# PWR_MGMT.net
KiCad netlist of a schematic drawn in Altium Designer
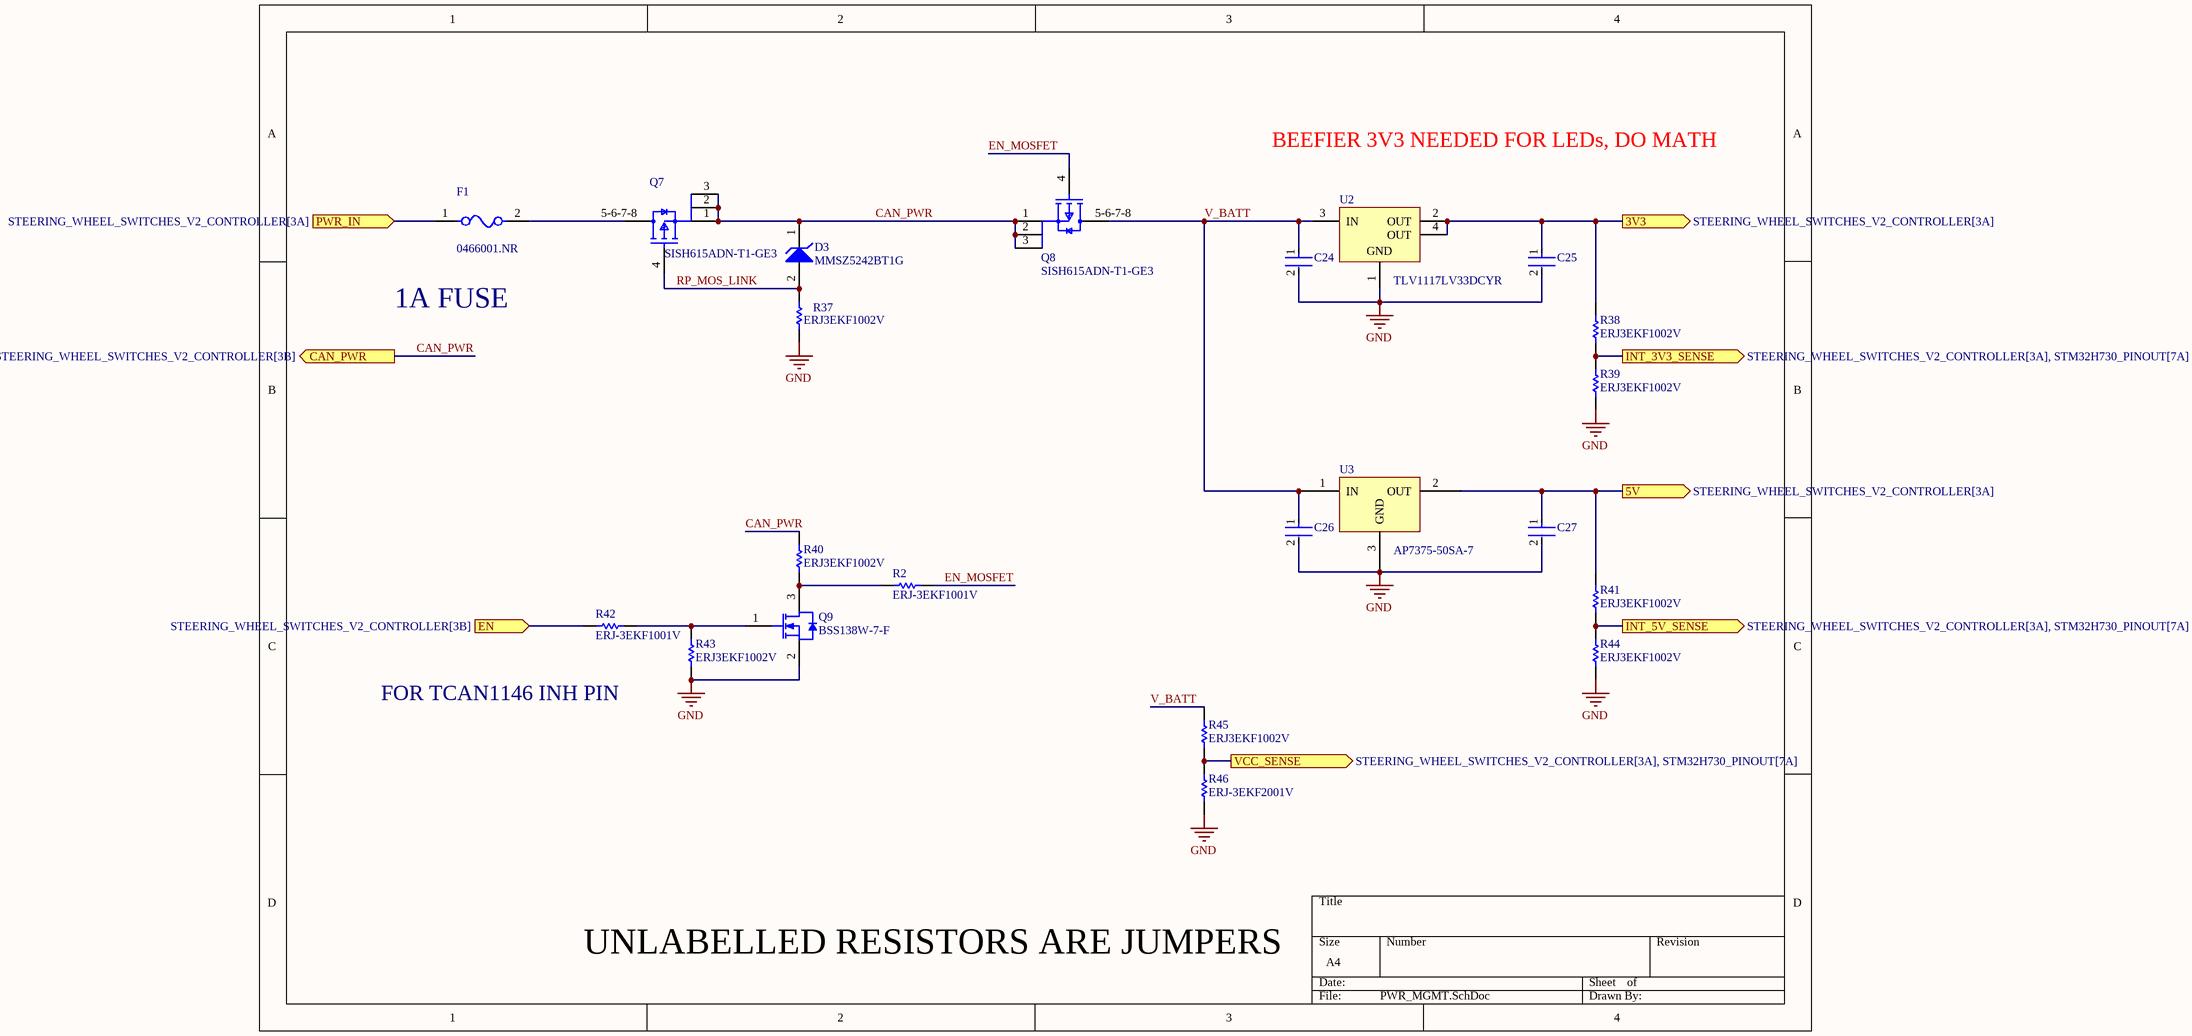
[diagram p0: PWR_MGMT.SchDoc]

(export (version "E")
  (design (tool "Eeschema 10.0.6"))
  (components
    (comp (ref "C24")
      (value "GRM188R61E106KA73D")
      (footprint "FP-GRM188-0_2-IPC_A")
      (description "Chip Multilayer Ceramic Capacitors for General Purpose, 0603, 10uF, X5R, 15%, 10%, 25V")
      (libsource (lib "Altium Content Vault") (part "11868f565c42a9108669ba33697ecf6"))
    )
    (comp (ref "C25")
      (value "GRM188R61E106KA73D")
      (footprint "FP-GRM188-0_2-IPC_A")
      (description "Chip Multilayer Ceramic Capacitors for General Purpose, 0603, 10uF, X5R, 15%, 10%, 25V")
      (libsource (lib "Altium Content Vault") (part "11868f565c42a9108669ba33697ecf6"))
    )
    (comp (ref "C26")
      (value "GRM188R61E106KA73D")
      (footprint "FP-GRM188-0_2-IPC_A")
      (description "Chip Multilayer Ceramic Capacitors for General Purpose, 0603, 10uF, X5R, 15%, 10%, 25V")
      (libsource (lib "Altium Content Vault") (part "11868f565c42a9108669ba33697ecf6"))
    )
    (comp (ref "C27")
      (value "GRM188R61E106KA73D")
      (footprint "FP-GRM188-0_2-IPC_A")
      (description "Chip Multilayer Ceramic Capacitors for General Purpose, 0603, 10uF, X5R, 15%, 10%, 25V")
      (libsource (lib "Altium Content Vault") (part "11868f565c42a9108669ba33697ecf6"))
    )
    (comp (ref "D3")
      (value "MMSZ5242BT1G")
      (footprint "ONSC-SOD-123-2-425-04_V")
      (description "Zener Voltage Regulator, 500 mW, 2-Pin SOD-123, Pb-Free, Tape and Reel")
      (fields (field (name "MANUFACTURER") "On Semiconductor"))
      (libsource (lib "Altium Content Vault") (part "ONSC-K1A2-2"))
    )
    (comp (ref "F1")
      (value "0466001.NR")
      (footprint "FP-0466-MFG")
      (description "FUSE BOARD MNT 1A 63VAC/VDC 1206")
      (fields
        (field (name "MANUFACTURER") "Littelfuse Inc")
        (field (name "OCTOPART") "https://octopart.com/0466001.nr-littelfuse-566005")
      )
      (libsource (lib "Altium Content Vault") (part "5bcf9b9f640e542cf0359d10258e979"))
    )
    (comp (ref "Q7")
      (value "SISH615ADN-T1-GE3")
      (footprint "SISH615ADN-T1-GE3-Footprint-1")
      (description "Trans MOSFET P-CH 20V 22.1A 8-Pin PowerPAK 1212 EP T/R")
      (libsource (lib "Space Concordia") (part "CMP-013-00036-4"))
    )
    (comp (ref "Q8")
      (value "SISH615ADN-T1-GE3")
      (footprint "SISH615ADN-T1-GE3-Footprint-1")
      (description "Trans MOSFET P-CH 20V 22.1A 8-Pin PowerPAK 1212 EP T/R")
      (libsource (lib "Space Concordia") (part "CMP-013-00036-4"))
    )
    (comp (ref "Q9")
      (value "BSS138W-7-F")
      (footprint "DIOD-SOT323-3_V")
      (fields (field (name "MANUFACTURER") "DiodesIncorporated"))
      (libsource (lib "Altium Content Vault") (part "NEMOS-GSD-3"))
    )
    (comp (ref "R2")
      (value "ERJ-3EKF1001V")
      (footprint "RESC1608X55X30LL15T15")
      (fields (field (name "MANUFACTURER") "Panasonic"))
      (libsource (lib "Altium Content Vault") (part "RES"))
    )
    (comp (ref "R37")
      (value "ERJ3EKF1002V")
      (footprint "RESC1609X55X30LL15T15")
      (description "Chip Resistor, 10 KOhm, +/- 1%, 0.1 W, -55 to 155 degC, 0603 (1608 Metric), RoHS, Tape and Reel")
      (fields (field (name "TOLERANCE") "1%") (field (name "MANUFACTURER") "Panasonic"))
      (libsource (lib "Altium Content Vault") (part "RES-2"))
    )
    (comp (ref "R38")
      (value "ERJ3EKF1002V")
      (footprint "RESC1609X55X30LL15T15")
      (description "Chip Resistor, 10 KOhm, +/- 1%, 0.1 W, -55 to 155 degC, 0603 (1608 Metric), RoHS, Tape and Reel")
      (fields (field (name "TOLERANCE") "1%") (field (name "MANUFACTURER") "Panasonic"))
      (libsource (lib "Altium Content Vault") (part "RES-2"))
    )
    (comp (ref "R39")
      (value "ERJ3EKF1002V")
      (footprint "RESC1609X55X30LL15T15")
      (description "Chip Resistor, 10 KOhm, +/- 1%, 0.1 W, -55 to 155 degC, 0603 (1608 Metric), RoHS, Tape and Reel")
      (fields (field (name "TOLERANCE") "1%") (field (name "MANUFACTURER") "Panasonic"))
      (libsource (lib "Altium Content Vault") (part "RES-2"))
    )
    (comp (ref "R40")
      (value "ERJ3EKF1002V")
      (footprint "RESC1609X55X30LL15T15")
      (description "Chip Resistor, 10 KOhm, +/- 1%, 0.1 W, -55 to 155 degC, 0603 (1608 Metric), RoHS, Tape and Reel")
      (fields (field (name "TOLERANCE") "1%") (field (name "MANUFACTURER") "Panasonic"))
      (libsource (lib "Altium Content Vault") (part "RES-2"))
    )
    (comp (ref "R41")
      (value "ERJ3EKF1002V")
      (footprint "RESC1609X55X30LL15T15")
      (description "Chip Resistor, 10 KOhm, +/- 1%, 0.1 W, -55 to 155 degC, 0603 (1608 Metric), RoHS, Tape and Reel")
      (fields (field (name "TOLERANCE") "1%") (field (name "MANUFACTURER") "Panasonic"))
      (libsource (lib "Altium Content Vault") (part "RES-2"))
    )
    (comp (ref "R42")
      (value "ERJ-3EKF1001V")
      (footprint "RESC1608X55X30LL15T15")
      (fields (field (name "MANUFACTURER") "Panasonic"))
      (libsource (lib "Altium Content Vault") (part "RES"))
    )
    (comp (ref "R43")
      (value "ERJ3EKF1002V")
      (footprint "RESC1609X55X30LL15T15")
      (description "Chip Resistor, 10 KOhm, +/- 1%, 0.1 W, -55 to 155 degC, 0603 (1608 Metric), RoHS, Tape and Reel")
      (fields (field (name "TOLERANCE") "1%") (field (name "MANUFACTURER") "Panasonic"))
      (libsource (lib "Altium Content Vault") (part "RES-2"))
    )
    (comp (ref "R44")
      (value "ERJ3EKF1002V")
      (footprint "RESC1609X55X30LL15T15")
      (description "Chip Resistor, 10 KOhm, +/- 1%, 0.1 W, -55 to 155 degC, 0603 (1608 Metric), RoHS, Tape and Reel")
      (fields (field (name "TOLERANCE") "1%") (field (name "MANUFACTURER") "Panasonic"))
      (libsource (lib "Altium Content Vault") (part "RES-2"))
    )
    (comp (ref "R45")
      (value "ERJ3EKF1002V")
      (footprint "RESC1609X55X30LL15T15")
      (description "Chip Resistor, 10 KOhm, +/- 1%, 0.1 W, -55 to 155 degC, 0603 (1608 Metric), RoHS, Tape and Reel")
      (fields (field (name "TOLERANCE") "1%") (field (name "MANUFACTURER") "Panasonic"))
      (libsource (lib "Altium Content Vault") (part "RES-2"))
    )
    (comp (ref "R46")
      (value "ERJ-3EKF2001V")
      (footprint "RESC1608X55X30ML15T15")
      (fields (field (name "MANUFACTURER") "Panasonic"))
      (libsource (lib "Altium Content Vault") (part "RES"))
    )
    (comp (ref "U2")
      (value "TLV1117LV33DCYR")
      (footprint "DCY0004A_N")
      (fields (field (name "MANUFACTURER") "Texas Instruments"))
      (libsource (lib "Altium Content Vault") (part "TI-TLV1117LV33DCY4"))
    )
    (comp (ref "U3")
      (value "AP7375-50SA-7")
      (footprint "AP7375-50SA-7-Footprint-1")
      (description "Ldo Cmos Lowcurr SOT23 T&r 3K")
      (libsource (lib "Space Concordia") (part "AP7375-50SA-7"))
    )
  )
  (nets
    (net (code "1") (name "/3V3") (class "Default")
      (node (ref "C25") (pin "1") (pinfunction "1_1") (pintype "passive"))
      (node (ref "R38") (pin "2") (pinfunction "2_2") (pintype "passive"))
      (node (ref "U2") (pin "2") (pinfunction "OUT_2") (pintype "power_in"))
      (node (ref "U2") (pin "4") (pinfunction "OUT_4") (pintype "power_in"))
    )
    (net (code "2") (name "/5V") (class "Default")
      (node (ref "C27") (pin "1") (pinfunction "1_1") (pintype "passive"))
      (node (ref "R41") (pin "2") (pinfunction "2_2") (pintype "passive"))
      (node (ref "U3") (pin "2") (pinfunction "OUT_2") (pintype "passive"))
    )
    (net (code "3") (name "/CAN_PWR") (class "Default")
      (node (ref "D3") (pin "1") (pinfunction "K_1") (pintype "passive"))
      (node (ref "Q7") (pin "1") (pinfunction "S_1") (pintype "passive"))
      (node (ref "Q7") (pin "2") (pinfunction "S_2") (pintype "passive"))
      (node (ref "Q7") (pin "3") (pinfunction "S_3") (pintype "passive"))
      (node (ref "Q8") (pin "1") (pinfunction "S_1") (pintype "passive"))
      (node (ref "Q8") (pin "2") (pinfunction "S_2") (pintype "passive"))
      (node (ref "Q8") (pin "3") (pinfunction "S_3") (pintype "passive"))
      (node (ref "R40") (pin "2") (pinfunction "2_2") (pintype "passive"))
    )
    (net (code "4") (name "/EN") (class "Default")
      (node (ref "R42") (pin "2") (pinfunction "2_2") (pintype "passive"))
    )
    (net (code "5") (name "/EN_MOSFET") (class "Default")
      (node (ref "Q8") (pin "4") (pinfunction "G_4") (pintype "passive"))
      (node (ref "R2") (pin "1") (pinfunction "1_1") (pintype "passive"))
    )
    (net (code "6") (name "/INT_3V3_SENSE") (class "Default")
      (node (ref "R38") (pin "1") (pinfunction "1_1") (pintype "passive"))
      (node (ref "R39") (pin "2") (pinfunction "2_2") (pintype "passive"))
    )
    (net (code "7") (name "/INT_5V_SENSE") (class "Default")
      (node (ref "R41") (pin "1") (pinfunction "1_1") (pintype "passive"))
      (node (ref "R44") (pin "1") (pinfunction "1_1") (pintype "passive"))
    )
    (net (code "8") (name "/PWR_IN") (class "Default")
      (node (ref "F1") (pin "1") (pinfunction "1_1") (pintype "passive"))
    )
    (net (code "9") (name "/RP_MOS_LINK") (class "Default")
      (node (ref "D3") (pin "2") (pinfunction "A_2") (pintype "passive"))
      (node (ref "Q7") (pin "4") (pinfunction "G_4") (pintype "passive"))
      (node (ref "R37") (pin "1") (pinfunction "1_1") (pintype "passive"))
    )
    (net (code "10") (name "/VCC_SENSE") (class "Default")
      (node (ref "R45") (pin "1") (pinfunction "1_1") (pintype "passive"))
      (node (ref "R46") (pin "2") (pinfunction "2_2") (pintype "passive"))
    )
    (net (code "11") (name "/V_BATT") (class "Default")
      (node (ref "C24") (pin "1") (pinfunction "1_1") (pintype "passive"))
      (node (ref "C26") (pin "1") (pinfunction "1_1") (pintype "passive"))
      (node (ref "Q8") (pin "5-6-7-8") (pinfunction "D_5-6-7-8") (pintype "passive"))
      (node (ref "R45") (pin "2") (pinfunction "2_2") (pintype "passive"))
      (node (ref "U2") (pin "3") (pinfunction "IN_3") (pintype "power_in"))
      (node (ref "U3") (pin "1") (pinfunction "IN_1") (pintype "passive"))
    )
    (net (code "12") (name "GND") (class "Default")
      (node (ref "C24") (pin "2") (pinfunction "2_2") (pintype "passive"))
      (node (ref "C25") (pin "2") (pinfunction "2_2") (pintype "passive"))
      (node (ref "C26") (pin "2") (pinfunction "2_2") (pintype "passive"))
      (node (ref "C27") (pin "2") (pinfunction "2_2") (pintype "passive"))
      (node (ref "Q9") (pin "2") (pinfunction "S_2") (pintype "passive"))
      (node (ref "R37") (pin "2") (pinfunction "2_2") (pintype "passive"))
      (node (ref "R39") (pin "1") (pinfunction "1_1") (pintype "passive"))
      (node (ref "R43") (pin "1") (pinfunction "1_1") (pintype "passive"))
      (node (ref "R44") (pin "2") (pinfunction "2_2") (pintype "passive"))
      (node (ref "R46") (pin "1") (pinfunction "1_1") (pintype "passive"))
      (node (ref "U2") (pin "1") (pinfunction "GND_1") (pintype "power_in"))
      (node (ref "U3") (pin "3") (pinfunction "GND_3") (pintype "passive"))
    )
    (net (code "13") (name "Net-(Q7-D)") (class "Default")
      (node (ref "F1") (pin "2") (pinfunction "2_2") (pintype "passive"))
      (node (ref "Q7") (pin "5-6-7-8") (pinfunction "D_5-6-7-8") (pintype "passive"))
    )
    (net (code "14") (name "Net-(Q9-D)") (class "Default")
      (node (ref "Q9") (pin "3") (pinfunction "D_3") (pintype "passive"))
      (node (ref "R2") (pin "2") (pinfunction "2_2") (pintype "passive"))
      (node (ref "R40") (pin "1") (pinfunction "1_1") (pintype "passive"))
    )
    (net (code "15") (name "Net-(Q9-G)") (class "Default")
      (node (ref "Q9") (pin "1") (pinfunction "G_1") (pintype "passive"))
      (node (ref "R42") (pin "1") (pinfunction "1_1") (pintype "passive"))
      (node (ref "R43") (pin "2") (pinfunction "2_2") (pintype "passive"))
    )
  )
)
